# Dino_Game.net
KiCad netlist of a schematic drawn in EAGLE
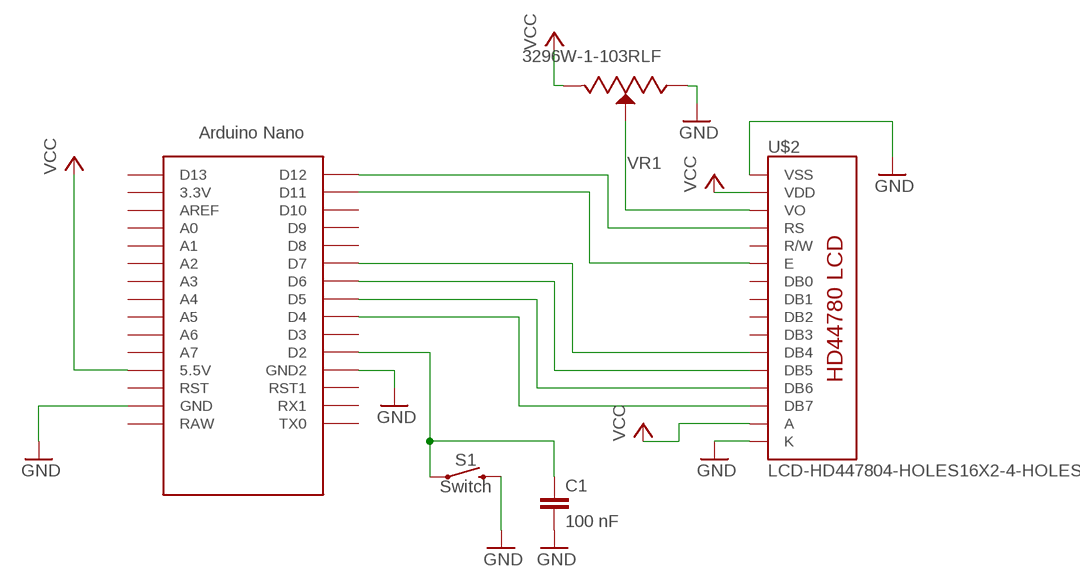
[diagram p0: schematic, sheet 1]

(export (version "E")
  (design (tool "Eeschema 10.0.6"))
  (components
    (comp (ref "C1")
      (value "100 nF")
      (footprint "eagle-import:C025-024X044")
      (libsource (lib "eagle-import") (part "C-EU025-024X044"))
    )
    (comp (ref "S1")
      (value "Switch")
      (footprint "eagle-import:TACTILE_SWITCH_PTH_12MM")
      (libsource (lib "eagle-import") (part "MOMENTARY-SWITCH-SPST-PTH-12MM"))
    )
    (comp (ref "U$1")
      (value "NANO")
      (footprint "eagle-import:NANO")
      (libsource (lib "eagle-import") (part "NANO"))
    )
    (comp (ref "U$2")
      (value "LCD-HD447804-HOLES16X2-4-HOLES")
      (footprint "eagle-import:LCD-16X2-4HOLES")
      (libsource (lib "eagle-import") (part "LCD-HD4478016X2-4-HOLES4-HOLES"))
    )
    (comp (ref "VR1")
      (value "3296W-1-103RLF")
      (footprint "eagle-import:TRIM_3296W-1-103RLF")
      (fields (field (name "MF") "Bourns"))
      (libsource (lib "eagle-import") (part "3296W-1-103RLF"))
    )
  )
  (nets
    (net (code "1") (name "GND") (class "Default")
      (node (ref "C1") (pin "2") (pinfunction "2_2") (pintype "passive"))
      (node (ref "S1") (pin "3") (pinfunction "2_3") (pintype "passive"))
      (node (ref "U$1") (pin "GND") (pinfunction "GND_GND") (pintype "bidirectional"))
      (node (ref "U$1") (pin "GND1") (pinfunction "GND2_GND1") (pintype "bidirectional"))
      (node (ref "U$2") (pin "1") (pinfunction "VSS_1") (pintype "power_in"))
      (node (ref "U$2") (pin "16") (pinfunction "K_16") (pintype "power_in"))
      (node (ref "VR1") (pin "1") (pinfunction "CCW_1") (pintype "passive"))
    )
    (net (code "2") (name "Net-(C1-Pad1)") (class "Default")
      (node (ref "C1") (pin "1") (pinfunction "1_1") (pintype "passive"))
      (node (ref "S1") (pin "1") (pinfunction "1_1") (pintype "passive"))
      (node (ref "U$1") (pin "D2") (pinfunction "D2_D2") (pintype "bidirectional"))
    )
    (net (code "3") (name "Net-(U$2-DB4)") (class "Default")
      (node (ref "U$1") (pin "D7") (pinfunction "D7_D7") (pintype "bidirectional"))
      (node (ref "U$2") (pin "11") (pinfunction "DB4_11") (pintype "bidirectional"))
    )
    (net (code "4") (name "Net-(U$2-DB5)") (class "Default")
      (node (ref "U$1") (pin "D6") (pinfunction "D6_D6") (pintype "bidirectional"))
      (node (ref "U$2") (pin "12") (pinfunction "DB5_12") (pintype "bidirectional"))
    )
    (net (code "5") (name "Net-(U$2-DB6)") (class "Default")
      (node (ref "U$1") (pin "D5") (pinfunction "D5_D5") (pintype "bidirectional"))
      (node (ref "U$2") (pin "13") (pinfunction "DB6_13") (pintype "bidirectional"))
    )
    (net (code "6") (name "Net-(U$2-DB7)") (class "Default")
      (node (ref "U$1") (pin "D4") (pinfunction "D4_D4") (pintype "bidirectional"))
      (node (ref "U$2") (pin "14") (pinfunction "DB7_14") (pintype "bidirectional"))
    )
    (net (code "7") (name "Net-(U$2-E)") (class "Default")
      (node (ref "U$1") (pin "D11") (pinfunction "D11_D11") (pintype "bidirectional"))
      (node (ref "U$2") (pin "6") (pinfunction "E_6") (pintype "input"))
    )
    (net (code "8") (name "Net-(U$2-RS)") (class "Default")
      (node (ref "U$1") (pin "D12") (pinfunction "D12_D12") (pintype "bidirectional"))
      (node (ref "U$2") (pin "4") (pinfunction "RS_4") (pintype "input"))
    )
    (net (code "9") (name "Net-(U$2-VO)") (class "Default")
      (node (ref "U$2") (pin "3") (pinfunction "VO_3") (pintype "bidirectional"))
      (node (ref "VR1") (pin "2") (pinfunction "WIPER_2") (pintype "passive"))
    )
    (net (code "10") (name "VCC") (class "Default")
      (node (ref "U$1") (pin "5V") (pinfunction "5.5V_5V") (pintype "bidirectional"))
      (node (ref "U$2") (pin "15") (pinfunction "A_15") (pintype "power_in"))
      (node (ref "U$2") (pin "2") (pinfunction "VDD_2") (pintype "power_in"))
      (node (ref "VR1") (pin "3") (pinfunction "CW_3") (pintype "passive"))
    )
    (net (code "11") (name "unconnected-(U$1-Pad3.3V)") (class "Default")
      (node (ref "U$1") (pin "3.3V") (pinfunction "3.3V_3.3V") (pintype "bidirectional"))
    )
    (net (code "12") (name "unconnected-(U$1-PadA0)") (class "Default")
      (node (ref "U$1") (pin "A0") (pinfunction "A0_A0") (pintype "bidirectional"))
    )
    (net (code "13") (name "unconnected-(U$1-PadA1)") (class "Default")
      (node (ref "U$1") (pin "A1") (pinfunction "A1_A1") (pintype "bidirectional"))
    )
    (net (code "14") (name "unconnected-(U$1-PadA2)") (class "Default")
      (node (ref "U$1") (pin "A2") (pinfunction "A2_A2") (pintype "bidirectional"))
    )
    (net (code "15") (name "unconnected-(U$1-PadA3)") (class "Default")
      (node (ref "U$1") (pin "A3") (pinfunction "A3_A3") (pintype "bidirectional"))
    )
    (net (code "16") (name "unconnected-(U$1-PadA4)") (class "Default")
      (node (ref "U$1") (pin "A4") (pinfunction "A4_A4") (pintype "bidirectional"))
    )
    (net (code "17") (name "unconnected-(U$1-PadA5)") (class "Default")
      (node (ref "U$1") (pin "A5") (pinfunction "A5_A5") (pintype "bidirectional"))
    )
    (net (code "18") (name "unconnected-(U$1-PadA6)") (class "Default")
      (node (ref "U$1") (pin "A6") (pinfunction "A6_A6") (pintype "bidirectional"))
    )
    (net (code "19") (name "unconnected-(U$1-PadA7)") (class "Default")
      (node (ref "U$1") (pin "A7") (pinfunction "A7_A7") (pintype "bidirectional"))
    )
    (net (code "20") (name "unconnected-(U$1-PadAREF)") (class "Default")
      (node (ref "U$1") (pin "AREF") (pinfunction "AREF_AREF") (pintype "bidirectional"))
    )
    (net (code "21") (name "unconnected-(U$1-PadD3)") (class "Default")
      (node (ref "U$1") (pin "D3") (pinfunction "D3_D3") (pintype "bidirectional"))
    )
    (net (code "22") (name "unconnected-(U$1-PadD8)") (class "Default")
      (node (ref "U$1") (pin "D8") (pinfunction "D8_D8") (pintype "bidirectional"))
    )
    (net (code "23") (name "unconnected-(U$1-PadD9)") (class "Default")
      (node (ref "U$1") (pin "D9") (pinfunction "D9_D9") (pintype "bidirectional"))
    )
    (net (code "24") (name "unconnected-(U$1-PadD10)") (class "Default")
      (node (ref "U$1") (pin "D10") (pinfunction "D10_D10") (pintype "bidirectional"))
    )
    (net (code "25") (name "unconnected-(U$1-PadD13)") (class "Default")
      (node (ref "U$1") (pin "D13") (pinfunction "D13_D13") (pintype "bidirectional"))
    )
    (net (code "26") (name "unconnected-(U$1-PadICSP1)") (class "Default")
      (node (ref "U$1") (pin "ICSP1") (pinfunction "ICSP1_ICSP1") (pintype "bidirectional"))
    )
    (net (code "27") (name "unconnected-(U$1-PadICSP2)") (class "Default")
      (node (ref "U$1") (pin "ICSP2") (pinfunction "ICSP2_ICSP2") (pintype "bidirectional"))
    )
    (net (code "28") (name "unconnected-(U$1-PadICSP3)") (class "Default")
      (node (ref "U$1") (pin "ICSP3") (pinfunction "ICSP3_ICSP3") (pintype "bidirectional"))
    )
    (net (code "29") (name "unconnected-(U$1-PadICSP4)") (class "Default")
      (node (ref "U$1") (pin "ICSP4") (pinfunction "ICSP4_ICSP4") (pintype "bidirectional"))
    )
    (net (code "30") (name "unconnected-(U$1-PadICSP5)") (class "Default")
      (node (ref "U$1") (pin "ICSP5") (pinfunction "ICSP5_ICSP5") (pintype "bidirectional"))
    )
    (net (code "31") (name "unconnected-(U$1-PadICSP6)") (class "Default")
      (node (ref "U$1") (pin "ICSP6") (pinfunction "ICSP6_ICSP6") (pintype "bidirectional"))
    )
    (net (code "32") (name "unconnected-(U$1-PadRAW)") (class "Default")
      (node (ref "U$1") (pin "RAW") (pinfunction "RAW_RAW") (pintype "bidirectional"))
    )
    (net (code "33") (name "unconnected-(U$1-PadRST)") (class "Default")
      (node (ref "U$1") (pin "RST") (pinfunction "RST_RST") (pintype "bidirectional"))
    )
    (net (code "34") (name "unconnected-(U$1-PadRST1)") (class "Default")
      (node (ref "U$1") (pin "RST1") (pinfunction "RST1_RST1") (pintype "bidirectional"))
    )
    (net (code "35") (name "unconnected-(U$1-PadRX1)") (class "Default")
      (node (ref "U$1") (pin "RX1") (pinfunction "RX1_RX1") (pintype "bidirectional"))
    )
    (net (code "36") (name "unconnected-(U$1-PadTX0)") (class "Default")
      (node (ref "U$1") (pin "TX0") (pinfunction "TX0_TX0") (pintype "bidirectional"))
    )
    (net (code "37") (name "unconnected-(U$2-DB0-Pad7)") (class "Default")
      (node (ref "U$2") (pin "7") (pinfunction "DB0_7") (pintype "bidirectional"))
    )
    (net (code "38") (name "unconnected-(U$2-DB1-Pad8)") (class "Default")
      (node (ref "U$2") (pin "8") (pinfunction "DB1_8") (pintype "bidirectional"))
    )
    (net (code "39") (name "unconnected-(U$2-DB2-Pad9)") (class "Default")
      (node (ref "U$2") (pin "9") (pinfunction "DB2_9") (pintype "bidirectional"))
    )
    (net (code "40") (name "unconnected-(U$2-DB3-Pad10)") (class "Default")
      (node (ref "U$2") (pin "10") (pinfunction "DB3_10") (pintype "bidirectional"))
    )
    (net (code "41") (name "unconnected-(U$2-R{slash}W-Pad5)") (class "Default")
      (node (ref "U$2") (pin "5") (pinfunction "R/W_5") (pintype "input"))
    )
  )
)
